# murdock_top.net
KiCad netlist of a schematic drawn in EAGLE
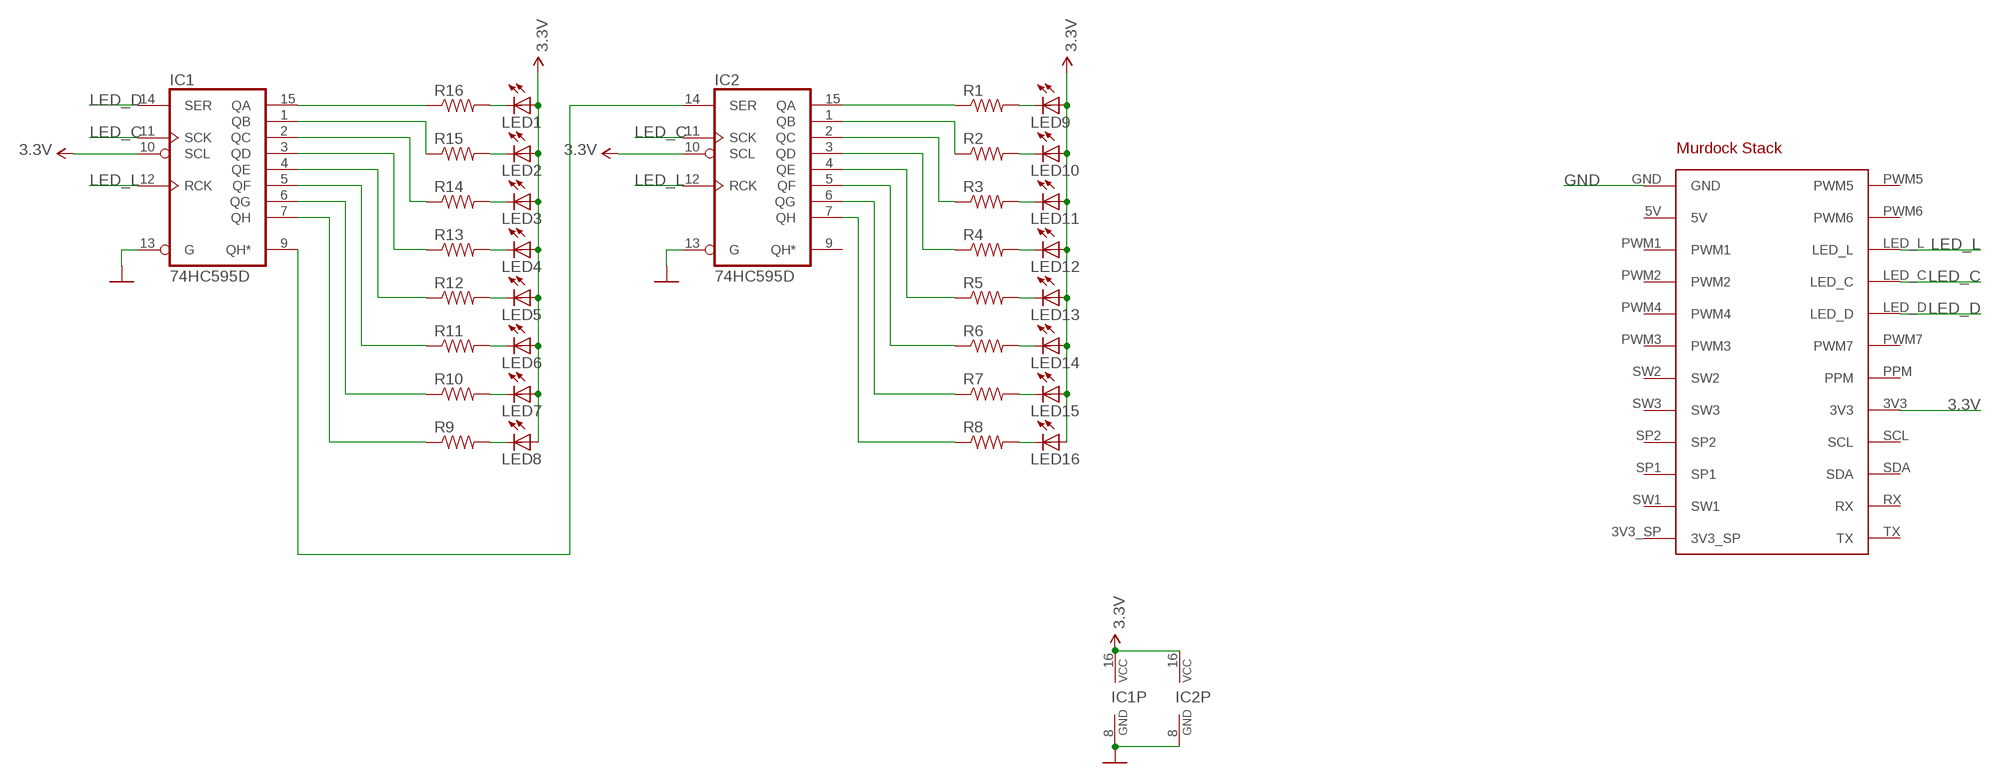
[diagram p0: schematic, sheet 1]

(export (version "E")
  (design (tool "Eeschema 10.0.6"))
  (components
    (comp (ref "IC1")
      (value "74HC595D")
      (footprint "eagle-import:SO16")
      (libsource (lib "eagle-import") (part "74595DHC"))
    )
    (comp (ref "IC2")
      (value "74HC595D")
      (footprint "eagle-import:SO16")
      (libsource (lib "eagle-import") (part "74595DHC"))
    )
    (comp (ref "LED1")
      (value "LGM47K")
      (footprint "eagle-import:LGM47K")
      (libsource (lib "eagle-import") (part "LGM47K"))
    )
    (comp (ref "LED2")
      (value "LGM47K")
      (footprint "eagle-import:LGM47K")
      (libsource (lib "eagle-import") (part "LGM47K"))
    )
    (comp (ref "LED3")
      (value "LGM47K")
      (footprint "eagle-import:LGM47K")
      (libsource (lib "eagle-import") (part "LGM47K"))
    )
    (comp (ref "LED4")
      (value "LGM47K")
      (footprint "eagle-import:LGM47K")
      (libsource (lib "eagle-import") (part "LGM47K"))
    )
    (comp (ref "LED5")
      (value "LGM47K")
      (footprint "eagle-import:LGM47K")
      (libsource (lib "eagle-import") (part "LGM47K"))
    )
    (comp (ref "LED6")
      (value "LGM47K")
      (footprint "eagle-import:LGM47K")
      (libsource (lib "eagle-import") (part "LGM47K"))
    )
    (comp (ref "LED7")
      (value "LGM47K")
      (footprint "eagle-import:LGM47K")
      (libsource (lib "eagle-import") (part "LGM47K"))
    )
    (comp (ref "LED8")
      (value "LGM47K")
      (footprint "eagle-import:LGM47K")
      (libsource (lib "eagle-import") (part "LGM47K"))
    )
    (comp (ref "LED9")
      (value "LGM47K")
      (footprint "eagle-import:LGM47K")
      (libsource (lib "eagle-import") (part "LGM47K"))
    )
    (comp (ref "LED10")
      (value "LGM47K")
      (footprint "eagle-import:LGM47K")
      (libsource (lib "eagle-import") (part "LGM47K"))
    )
    (comp (ref "LED11")
      (value "LGM47K")
      (footprint "eagle-import:LGM47K")
      (libsource (lib "eagle-import") (part "LGM47K"))
    )
    (comp (ref "LED12")
      (value "LGM47K")
      (footprint "eagle-import:LGM47K")
      (libsource (lib "eagle-import") (part "LGM47K"))
    )
    (comp (ref "LED13")
      (value "LGM47K")
      (footprint "eagle-import:LGM47K")
      (libsource (lib "eagle-import") (part "LGM47K"))
    )
    (comp (ref "LED14")
      (value "LGM47K")
      (footprint "eagle-import:LGM47K")
      (libsource (lib "eagle-import") (part "LGM47K"))
    )
    (comp (ref "LED15")
      (value "LGM47K")
      (footprint "eagle-import:LGM47K")
      (libsource (lib "eagle-import") (part "LGM47K"))
    )
    (comp (ref "LED16")
      (value "LGM47K")
      (footprint "eagle-import:LGM47K")
      (libsource (lib "eagle-import") (part "LGM47K"))
    )
    (comp (ref "R1")
      (value "RESISTOR0402-RES")
      (footprint "eagle-import:0402-RES")
      (libsource (lib "eagle-import") (part "RESISTOR0402-RES"))
    )
    (comp (ref "R2")
      (value "RESISTOR0402-RES")
      (footprint "eagle-import:0402-RES")
      (libsource (lib "eagle-import") (part "RESISTOR0402-RES"))
    )
    (comp (ref "R3")
      (value "RESISTOR0402-RES")
      (footprint "eagle-import:0402-RES")
      (libsource (lib "eagle-import") (part "RESISTOR0402-RES"))
    )
    (comp (ref "R4")
      (value "RESISTOR0402-RES")
      (footprint "eagle-import:0402-RES")
      (libsource (lib "eagle-import") (part "RESISTOR0402-RES"))
    )
    (comp (ref "R5")
      (value "RESISTOR0402-RES")
      (footprint "eagle-import:0402-RES")
      (libsource (lib "eagle-import") (part "RESISTOR0402-RES"))
    )
    (comp (ref "R6")
      (value "RESISTOR0402-RES")
      (footprint "eagle-import:0402-RES")
      (libsource (lib "eagle-import") (part "RESISTOR0402-RES"))
    )
    (comp (ref "R7")
      (value "RESISTOR0402-RES")
      (footprint "eagle-import:0402-RES")
      (libsource (lib "eagle-import") (part "RESISTOR0402-RES"))
    )
    (comp (ref "R8")
      (value "RESISTOR0402-RES")
      (footprint "eagle-import:0402-RES")
      (libsource (lib "eagle-import") (part "RESISTOR0402-RES"))
    )
    (comp (ref "R9")
      (value "RESISTOR0402-RES")
      (footprint "eagle-import:0402-RES")
      (libsource (lib "eagle-import") (part "RESISTOR0402-RES"))
    )
    (comp (ref "R10")
      (value "RESISTOR0402-RES")
      (footprint "eagle-import:0402-RES")
      (libsource (lib "eagle-import") (part "RESISTOR0402-RES"))
    )
    (comp (ref "R11")
      (value "RESISTOR0402-RES")
      (footprint "eagle-import:0402-RES")
      (libsource (lib "eagle-import") (part "RESISTOR0402-RES"))
    )
    (comp (ref "R12")
      (value "RESISTOR0402-RES")
      (footprint "eagle-import:0402-RES")
      (libsource (lib "eagle-import") (part "RESISTOR0402-RES"))
    )
    (comp (ref "R13")
      (value "RESISTOR0402-RES")
      (footprint "eagle-import:0402-RES")
      (libsource (lib "eagle-import") (part "RESISTOR0402-RES"))
    )
    (comp (ref "R14")
      (value "RESISTOR0402-RES")
      (footprint "eagle-import:0402-RES")
      (libsource (lib "eagle-import") (part "RESISTOR0402-RES"))
    )
    (comp (ref "R15")
      (value "RESISTOR0402-RES")
      (footprint "eagle-import:0402-RES")
      (libsource (lib "eagle-import") (part "RESISTOR0402-RES"))
    )
    (comp (ref "R16")
      (value "RESISTOR0402-RES")
      (footprint "eagle-import:0402-RES")
      (libsource (lib "eagle-import") (part "RESISTOR0402-RES"))
    )
    (comp (ref "X1")
      (value "MURDOCK_STACK")
      (footprint "eagle-import:MURDOCK_STACK")
      (libsource (lib "eagle-import") (part "MURDOCK_STACK"))
    )
  )
  (nets
    (net (code "1") (name "/LED_C") (class "Default")
      (node (ref "IC1") (pin "11") (pinfunction "SCK_11") (pintype "input"))
      (node (ref "IC2") (pin "11") (pinfunction "SCK_11") (pintype "input"))
      (node (ref "X1") (pin "LED_C") (pinfunction "LED_C_LED_C") (pintype "bidirectional"))
    )
    (net (code "2") (name "/LED_D") (class "Default")
      (node (ref "IC1") (pin "14") (pinfunction "SER_14") (pintype "input"))
      (node (ref "X1") (pin "LED_D") (pinfunction "LED_D_LED_D") (pintype "bidirectional"))
    )
    (net (code "3") (name "/LED_L") (class "Default")
      (node (ref "IC1") (pin "12") (pinfunction "RCK_12") (pintype "input"))
      (node (ref "IC2") (pin "12") (pinfunction "RCK_12") (pintype "input"))
      (node (ref "X1") (pin "LED_L") (pinfunction "LED_L_LED_L") (pintype "bidirectional"))
    )
    (net (code "4") (name "3.3V") (class "Default")
      (node (ref "IC1") (pin "10") (pinfunction "SCL_10") (pintype "input"))
      (node (ref "IC1") (pin "16") (pinfunction "VCC_16") (pintype "power_in"))
      (node (ref "IC2") (pin "10") (pinfunction "SCL_10") (pintype "input"))
      (node (ref "IC2") (pin "16") (pinfunction "VCC_16") (pintype "power_in"))
      (node (ref "LED1") (pin "A") (pinfunction "A_A") (pintype "passive"))
      (node (ref "LED10") (pin "A") (pinfunction "A_A") (pintype "passive"))
      (node (ref "LED11") (pin "A") (pinfunction "A_A") (pintype "passive"))
      (node (ref "LED12") (pin "A") (pinfunction "A_A") (pintype "passive"))
      (node (ref "LED13") (pin "A") (pinfunction "A_A") (pintype "passive"))
      (node (ref "LED14") (pin "A") (pinfunction "A_A") (pintype "passive"))
      (node (ref "LED15") (pin "A") (pinfunction "A_A") (pintype "passive"))
      (node (ref "LED16") (pin "A") (pinfunction "A_A") (pintype "passive"))
      (node (ref "LED2") (pin "A") (pinfunction "A_A") (pintype "passive"))
      (node (ref "LED3") (pin "A") (pinfunction "A_A") (pintype "passive"))
      (node (ref "LED4") (pin "A") (pinfunction "A_A") (pintype "passive"))
      (node (ref "LED5") (pin "A") (pinfunction "A_A") (pintype "passive"))
      (node (ref "LED6") (pin "A") (pinfunction "A_A") (pintype "passive"))
      (node (ref "LED7") (pin "A") (pinfunction "A_A") (pintype "passive"))
      (node (ref "LED8") (pin "A") (pinfunction "A_A") (pintype "passive"))
      (node (ref "LED9") (pin "A") (pinfunction "A_A") (pintype "passive"))
      (node (ref "X1") (pin "3V3") (pinfunction "3V3_3V3") (pintype "bidirectional"))
    )
    (net (code "5") (name "GND") (class "Default")
      (node (ref "IC1") (pin "13") (pinfunction "G_13") (pintype "input"))
      (node (ref "IC1") (pin "8") (pinfunction "GND_8") (pintype "power_in"))
      (node (ref "IC2") (pin "13") (pinfunction "G_13") (pintype "input"))
      (node (ref "IC2") (pin "8") (pinfunction "GND_8") (pintype "power_in"))
      (node (ref "X1") (pin "GND") (pinfunction "GND_GND") (pintype "bidirectional"))
    )
    (net (code "6") (name "Net-(IC1A-QA)") (class "Default")
      (node (ref "IC1") (pin "15") (pinfunction "QA_15") (pintype "tri_state"))
      (node (ref "R16") (pin "1") (pinfunction "1_1") (pintype "passive"))
    )
    (net (code "7") (name "Net-(IC1A-QB)") (class "Default")
      (node (ref "IC1") (pin "1") (pinfunction "QB_1") (pintype "tri_state"))
      (node (ref "R15") (pin "1") (pinfunction "1_1") (pintype "passive"))
    )
    (net (code "8") (name "Net-(IC1A-QC)") (class "Default")
      (node (ref "IC1") (pin "2") (pinfunction "QC_2") (pintype "tri_state"))
      (node (ref "R14") (pin "1") (pinfunction "1_1") (pintype "passive"))
    )
    (net (code "9") (name "Net-(IC1A-QD)") (class "Default")
      (node (ref "IC1") (pin "3") (pinfunction "QD_3") (pintype "tri_state"))
      (node (ref "R13") (pin "1") (pinfunction "1_1") (pintype "passive"))
    )
    (net (code "10") (name "Net-(IC1A-QE)") (class "Default")
      (node (ref "IC1") (pin "4") (pinfunction "QE_4") (pintype "tri_state"))
      (node (ref "R12") (pin "1") (pinfunction "1_1") (pintype "passive"))
    )
    (net (code "11") (name "Net-(IC1A-QF)") (class "Default")
      (node (ref "IC1") (pin "5") (pinfunction "QF_5") (pintype "tri_state"))
      (node (ref "R11") (pin "1") (pinfunction "1_1") (pintype "passive"))
    )
    (net (code "12") (name "Net-(IC1A-QG)") (class "Default")
      (node (ref "IC1") (pin "6") (pinfunction "QG_6") (pintype "tri_state"))
      (node (ref "R10") (pin "1") (pinfunction "1_1") (pintype "passive"))
    )
    (net (code "13") (name "Net-(IC1A-QH)") (class "Default")
      (node (ref "IC1") (pin "7") (pinfunction "QH_7") (pintype "tri_state"))
      (node (ref "R9") (pin "1") (pinfunction "1_1") (pintype "passive"))
    )
    (net (code "14") (name "Net-(IC1A-QH*)") (class "Default")
      (node (ref "IC1") (pin "9") (pinfunction "QH*_9") (pintype "tri_state"))
      (node (ref "IC2") (pin "14") (pinfunction "SER_14") (pintype "input"))
    )
    (net (code "15") (name "Net-(IC2A-QA)") (class "Default")
      (node (ref "IC2") (pin "15") (pinfunction "QA_15") (pintype "tri_state"))
      (node (ref "R1") (pin "1") (pinfunction "1_1") (pintype "passive"))
    )
    (net (code "16") (name "Net-(IC2A-QB)") (class "Default")
      (node (ref "IC2") (pin "1") (pinfunction "QB_1") (pintype "tri_state"))
      (node (ref "R2") (pin "1") (pinfunction "1_1") (pintype "passive"))
    )
    (net (code "17") (name "Net-(IC2A-QC)") (class "Default")
      (node (ref "IC2") (pin "2") (pinfunction "QC_2") (pintype "tri_state"))
      (node (ref "R3") (pin "1") (pinfunction "1_1") (pintype "passive"))
    )
    (net (code "18") (name "Net-(IC2A-QD)") (class "Default")
      (node (ref "IC2") (pin "3") (pinfunction "QD_3") (pintype "tri_state"))
      (node (ref "R4") (pin "1") (pinfunction "1_1") (pintype "passive"))
    )
    (net (code "19") (name "Net-(IC2A-QE)") (class "Default")
      (node (ref "IC2") (pin "4") (pinfunction "QE_4") (pintype "tri_state"))
      (node (ref "R5") (pin "1") (pinfunction "1_1") (pintype "passive"))
    )
    (net (code "20") (name "Net-(IC2A-QF)") (class "Default")
      (node (ref "IC2") (pin "5") (pinfunction "QF_5") (pintype "tri_state"))
      (node (ref "R6") (pin "1") (pinfunction "1_1") (pintype "passive"))
    )
    (net (code "21") (name "Net-(IC2A-QG)") (class "Default")
      (node (ref "IC2") (pin "6") (pinfunction "QG_6") (pintype "tri_state"))
      (node (ref "R7") (pin "1") (pinfunction "1_1") (pintype "passive"))
    )
    (net (code "22") (name "Net-(IC2A-QH)") (class "Default")
      (node (ref "IC2") (pin "7") (pinfunction "QH_7") (pintype "tri_state"))
      (node (ref "R8") (pin "1") (pinfunction "1_1") (pintype "passive"))
    )
    (net (code "23") (name "Net-(LED1-C)") (class "Default")
      (node (ref "LED1") (pin "K") (pinfunction "C_K") (pintype "passive"))
      (node (ref "R16") (pin "2") (pinfunction "2_2") (pintype "passive"))
    )
    (net (code "24") (name "Net-(LED2-C)") (class "Default")
      (node (ref "LED2") (pin "K") (pinfunction "C_K") (pintype "passive"))
      (node (ref "R15") (pin "2") (pinfunction "2_2") (pintype "passive"))
    )
    (net (code "25") (name "Net-(LED3-C)") (class "Default")
      (node (ref "LED3") (pin "K") (pinfunction "C_K") (pintype "passive"))
      (node (ref "R14") (pin "2") (pinfunction "2_2") (pintype "passive"))
    )
    (net (code "26") (name "Net-(LED4-C)") (class "Default")
      (node (ref "LED4") (pin "K") (pinfunction "C_K") (pintype "passive"))
      (node (ref "R13") (pin "2") (pinfunction "2_2") (pintype "passive"))
    )
    (net (code "27") (name "Net-(LED5-C)") (class "Default")
      (node (ref "LED5") (pin "K") (pinfunction "C_K") (pintype "passive"))
      (node (ref "R12") (pin "2") (pinfunction "2_2") (pintype "passive"))
    )
    (net (code "28") (name "Net-(LED6-C)") (class "Default")
      (node (ref "LED6") (pin "K") (pinfunction "C_K") (pintype "passive"))
      (node (ref "R11") (pin "2") (pinfunction "2_2") (pintype "passive"))
    )
    (net (code "29") (name "Net-(LED7-C)") (class "Default")
      (node (ref "LED7") (pin "K") (pinfunction "C_K") (pintype "passive"))
      (node (ref "R10") (pin "2") (pinfunction "2_2") (pintype "passive"))
    )
    (net (code "30") (name "Net-(LED8-C)") (class "Default")
      (node (ref "LED8") (pin "K") (pinfunction "C_K") (pintype "passive"))
      (node (ref "R9") (pin "2") (pinfunction "2_2") (pintype "passive"))
    )
    (net (code "31") (name "Net-(LED9-C)") (class "Default")
      (node (ref "LED9") (pin "K") (pinfunction "C_K") (pintype "passive"))
      (node (ref "R1") (pin "2") (pinfunction "2_2") (pintype "passive"))
    )
    (net (code "32") (name "Net-(LED10-C)") (class "Default")
      (node (ref "LED10") (pin "K") (pinfunction "C_K") (pintype "passive"))
      (node (ref "R2") (pin "2") (pinfunction "2_2") (pintype "passive"))
    )
    (net (code "33") (name "Net-(LED11-C)") (class "Default")
      (node (ref "LED11") (pin "K") (pinfunction "C_K") (pintype "passive"))
      (node (ref "R3") (pin "2") (pinfunction "2_2") (pintype "passive"))
    )
    (net (code "34") (name "Net-(LED12-C)") (class "Default")
      (node (ref "LED12") (pin "K") (pinfunction "C_K") (pintype "passive"))
      (node (ref "R4") (pin "2") (pinfunction "2_2") (pintype "passive"))
    )
    (net (code "35") (name "Net-(LED13-C)") (class "Default")
      (node (ref "LED13") (pin "K") (pinfunction "C_K") (pintype "passive"))
      (node (ref "R5") (pin "2") (pinfunction "2_2") (pintype "passive"))
    )
    (net (code "36") (name "Net-(LED14-C)") (class "Default")
      (node (ref "LED14") (pin "K") (pinfunction "C_K") (pintype "passive"))
      (node (ref "R6") (pin "2") (pinfunction "2_2") (pintype "passive"))
    )
    (net (code "37") (name "Net-(LED15-C)") (class "Default")
      (node (ref "LED15") (pin "K") (pinfunction "C_K") (pintype "passive"))
      (node (ref "R7") (pin "2") (pinfunction "2_2") (pintype "passive"))
    )
    (net (code "38") (name "Net-(LED16-C)") (class "Default")
      (node (ref "LED16") (pin "K") (pinfunction "C_K") (pintype "passive"))
      (node (ref "R8") (pin "2") (pinfunction "2_2") (pintype "passive"))
    )
    (net (code "39") (name "unconnected-(IC2A-QH*-Pad9)") (class "Default")
      (node (ref "IC2") (pin "9") (pinfunction "QH*_9") (pintype "tri_state"))
    )
    (net (code "40") (name "unconnected-(X1-Pad3V3_SP)") (class "Default")
      (node (ref "X1") (pin "3V3_SP") (pinfunction "3V3_SP_3V3_SP") (pintype "bidirectional"))
    )
    (net (code "41") (name "unconnected-(X1-Pad5V)") (class "Default")
      (node (ref "X1") (pin "5V") (pinfunction "5V_5V") (pintype "bidirectional"))
    )
    (net (code "42") (name "unconnected-(X1-PadPPM)") (class "Default")
      (node (ref "X1") (pin "PPM") (pinfunction "PPM_PPM") (pintype "bidirectional"))
    )
    (net (code "43") (name "unconnected-(X1-PadPWM1)") (class "Default")
      (node (ref "X1") (pin "PWM1") (pinfunction "PWM1_PWM1") (pintype "bidirectional"))
    )
    (net (code "44") (name "unconnected-(X1-PadPWM2)") (class "Default")
      (node (ref "X1") (pin "PWM2") (pinfunction "PWM2_PWM2") (pintype "bidirectional"))
    )
    (net (code "45") (name "unconnected-(X1-PadPWM3)") (class "Default")
      (node (ref "X1") (pin "PWM3") (pinfunction "PWM3_PWM3") (pintype "bidirectional"))
    )
    (net (code "46") (name "unconnected-(X1-PadPWM4)") (class "Default")
      (node (ref "X1") (pin "PWM4") (pinfunction "PWM4_PWM4") (pintype "bidirectional"))
    )
    (net (code "47") (name "unconnected-(X1-PadPWM5)") (class "Default")
      (node (ref "X1") (pin "PWM5") (pinfunction "PWM5_PWM5") (pintype "bidirectional"))
    )
    (net (code "48") (name "unconnected-(X1-PadPWM6)") (class "Default")
      (node (ref "X1") (pin "PWM6") (pinfunction "PWM6_PWM6") (pintype "bidirectional"))
    )
    (net (code "49") (name "unconnected-(X1-PadPWM7)") (class "Default")
      (node (ref "X1") (pin "PWM7") (pinfunction "PWM7_PWM7") (pintype "bidirectional"))
    )
    (net (code "50") (name "unconnected-(X1-PadRX)") (class "Default")
      (node (ref "X1") (pin "RX") (pinfunction "RX_RX") (pintype "bidirectional"))
    )
    (net (code "51") (name "unconnected-(X1-PadSCL)") (class "Default")
      (node (ref "X1") (pin "SCL") (pinfunction "SCL_SCL") (pintype "bidirectional"))
    )
    (net (code "52") (name "unconnected-(X1-PadSDA)") (class "Default")
      (node (ref "X1") (pin "SDA") (pinfunction "SDA_SDA") (pintype "bidirectional"))
    )
    (net (code "53") (name "unconnected-(X1-PadSP1)") (class "Default")
      (node (ref "X1") (pin "SP1") (pinfunction "SP1_SP1") (pintype "bidirectional"))
    )
    (net (code "54") (name "unconnected-(X1-PadSP2)") (class "Default")
      (node (ref "X1") (pin "SP2") (pinfunction "SP2_SP2") (pintype "bidirectional"))
    )
    (net (code "55") (name "unconnected-(X1-PadSW1)") (class "Default")
      (node (ref "X1") (pin "SW1") (pinfunction "SW1_SW1") (pintype "bidirectional"))
    )
    (net (code "56") (name "unconnected-(X1-PadSW2)") (class "Default")
      (node (ref "X1") (pin "SW2") (pinfunction "SW2_SW2") (pintype "bidirectional"))
    )
    (net (code "57") (name "unconnected-(X1-PadSW3)") (class "Default")
      (node (ref "X1") (pin "SW3") (pinfunction "SW3_SW3") (pintype "bidirectional"))
    )
    (net (code "58") (name "unconnected-(X1-PadTX)") (class "Default")
      (node (ref "X1") (pin "TX") (pinfunction "TX_TX") (pintype "bidirectional"))
    )
  )
)
